# IMU.net
KiCad netlist of a schematic drawn in Altium Designer
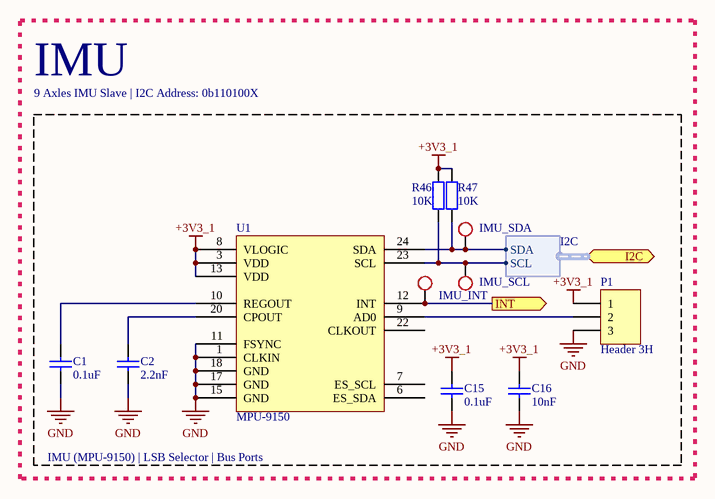
[diagram p0: IMU.SchDoc]

(export (version "E")
  (design (tool "Eeschema 10.0.6"))
  (components
    (comp (ref "C1")
      (value "0.1uF")
      (footprint "C0805")
      (description "Capacitor (Semiconductor SIM Model)")
      (fields (field (name "PUBLISHER") "Altium Limited"))
      (libsource (lib "Miscellaneous Devices") (part "Cap Semi"))
    )
    (comp (ref "C2")
      (value "2.2nF")
      (footprint "C0805")
      (description "Capacitor (Semiconductor SIM Model)")
      (fields (field (name "PUBLISHER") "Altium Limited"))
      (libsource (lib "Miscellaneous Devices") (part "Cap Semi"))
    )
    (comp (ref "C15")
      (value "0.1uF")
      (footprint "C0805")
      (description "Capacitor (Semiconductor SIM Model)")
      (fields (field (name "PUBLISHER") "Altium Limited"))
      (libsource (lib "Miscellaneous Devices") (part "Cap Semi"))
    )
    (comp (ref "C16")
      (value "10nF")
      (footprint "C0805")
      (description "Capacitor (Semiconductor SIM Model)")
      (fields (field (name "PUBLISHER") "Altium Limited"))
      (libsource (lib "Miscellaneous Devices") (part "Cap Semi"))
    )
    (comp (ref "IMU_INT")
      (value "Test Point")
      (footprint "TP1")
      (description "Test Point for Osciloscope measurements")
      (libsource (lib "CustomLibrary") (part "Test Point"))
    )
    (comp (ref "IMU_SCL")
      (value "Test Point")
      (footprint "TP1")
      (description "Test Point for Osciloscope measurements")
      (libsource (lib "CustomLibrary") (part "Test Point"))
    )
    (comp (ref "IMU_SDA")
      (value "Test Point")
      (footprint "TP1")
      (description "Test Point for Osciloscope measurements")
      (libsource (lib "CustomLibrary") (part "Test Point"))
    )
    (comp (ref "P1")
      (value "Header 3H")
      (footprint "HDR1X3H")
      (description "Header, 3-Pin, Right Angle")
      (fields (field (name "PUBLISHER") "Altium Limited"))
      (libsource (lib "Miscellaneous Connectors") (part "Header 3H"))
    )
    (comp (ref "R46") (value "10K") (footprint "RES1206") (libsource (lib "CustomLibrary") (part "RES")))
    (comp (ref "R47") (value "10K") (footprint "RES1206") (libsource (lib "CustomLibrary") (part "RES")))
    (comp (ref "U1")
      (value "MPU-9150")
      (footprint "LGA-24")
      (description "InveSense MPU-9150 IMU 9 axles")
      (libsource (lib "CustomLibrary") (part "MPU-9150"))
    )
  )
  (nets
    (net (code "2") (name "+3V3_1") (class "Default")
      (node (ref "C15") (pin "2") (pinfunction "2_2") (pintype "passive"))
      (node (ref "C16") (pin "2") (pinfunction "2_2") (pintype "passive"))
      (node (ref "P1") (pin "1") (pinfunction "1_1") (pintype "passive"))
      (node (ref "R46") (pin "1") (pinfunction "1_1") (pintype "passive"))
      (node (ref "R47") (pin "1") (pinfunction "1_1") (pintype "passive"))
      (node (ref "U1") (pin "13") (pinfunction "VDD_13") (pintype "power_in"))
      (node (ref "U1") (pin "3") (pinfunction "VDD_3") (pintype "power_in"))
      (node (ref "U1") (pin "8") (pinfunction "VLOGIC_8") (pintype "power_in"))
    )
    (net (code "3") (name "/INT") (class "Default")
      (node (ref "IMU_INT") (pin "1") (pinfunction "1_1") (pintype "passive"))
      (node (ref "U1") (pin "12") (pinfunction "INT_12") (pintype "passive"))
    )
    (net (code "5") (name "GND") (class "Default")
      (node (ref "C1") (pin "1") (pinfunction "1_1") (pintype "passive"))
      (node (ref "C15") (pin "1") (pinfunction "1_1") (pintype "passive"))
      (node (ref "C16") (pin "1") (pinfunction "1_1") (pintype "passive"))
      (node (ref "C2") (pin "1") (pinfunction "1_1") (pintype "passive"))
      (node (ref "P1") (pin "3") (pinfunction "3_3") (pintype "passive"))
      (node (ref "U1") (pin "1") (pinfunction "CLKIN_1") (pintype "passive"))
      (node (ref "U1") (pin "11") (pinfunction "FSYNC_11") (pintype "passive"))
      (node (ref "U1") (pin "15") (pinfunction "GND_15") (pintype "power_in"))
      (node (ref "U1") (pin "17") (pinfunction "GND_17") (pintype "power_in"))
      (node (ref "U1") (pin "18") (pinfunction "GND_18") (pintype "power_in"))
    )
    (net (code "6") (name "Net-(U1-AD0)") (class "Default")
      (node (ref "P1") (pin "2") (pinfunction "2_2") (pintype "passive"))
      (node (ref "U1") (pin "9") (pinfunction "AD0_9") (pintype "passive"))
    )
    (net (code "7") (name "Net-(U1-CPOUT)") (class "Default")
      (node (ref "C2") (pin "2") (pinfunction "2_2") (pintype "passive"))
      (node (ref "U1") (pin "20") (pinfunction "CPOUT_20") (pintype "passive"))
    )
    (net (code "8") (name "Net-(U1-REGOUT)") (class "Default")
      (node (ref "C1") (pin "2") (pinfunction "2_2") (pintype "passive"))
      (node (ref "U1") (pin "10") (pinfunction "REGOUT_10") (pintype "passive"))
    )
    (net (code "9") (name "Net-(U1-SCL)") (class "Default")
      (node (ref "IMU_SCL") (pin "1") (pinfunction "1_1") (pintype "passive"))
      (node (ref "R46") (pin "2") (pinfunction "2_2") (pintype "passive"))
      (node (ref "U1") (pin "23") (pinfunction "SCL_23") (pintype "passive"))
    )
    (net (code "10") (name "Net-(U1-SDA)") (class "Default")
      (node (ref "IMU_SDA") (pin "1") (pinfunction "1_1") (pintype "passive"))
      (node (ref "R47") (pin "2") (pinfunction "2_2") (pintype "passive"))
      (node (ref "U1") (pin "24") (pinfunction "SDA_24") (pintype "passive"))
    )
    (net (code "11") (name "unconnected-(U1-CLKOUT-Pad22)") (class "Default")
      (node (ref "U1") (pin "22") (pinfunction "CLKOUT_22") (pintype "passive"))
    )
    (net (code "12") (name "unconnected-(U1-ES_SCL-Pad7)") (class "Default")
      (node (ref "U1") (pin "7") (pinfunction "ES_SCL_7") (pintype "passive"))
    )
    (net (code "13") (name "unconnected-(U1-ES_SDA-Pad6)") (class "Default")
      (node (ref "U1") (pin "6") (pinfunction "ES_SDA_6") (pintype "passive"))
    )
  )
)
